# UCube_v2_Tower2.net
KiCad netlist of a schematic drawn in EAGLE
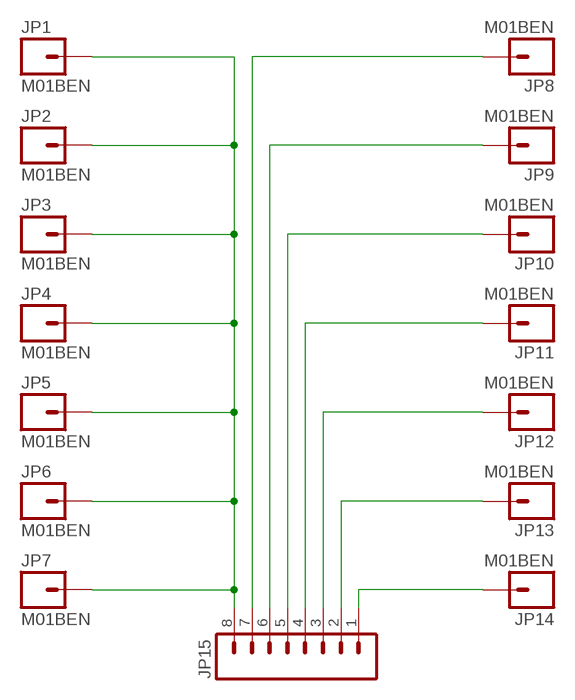
[diagram p0: schematic, sheet 1]

(export (version "E")
  (design (tool "Eeschema 10.0.6"))
  (components
    (comp (ref "JP1")
      (value "M01BEN")
      (footprint "eagle-import:1X01-BEN")
      (libsource (lib "eagle-import") (part "M01BEN"))
    )
    (comp (ref "JP2")
      (value "M01BEN")
      (footprint "eagle-import:1X01-BEN")
      (libsource (lib "eagle-import") (part "M01BEN"))
    )
    (comp (ref "JP3")
      (value "M01BEN")
      (footprint "eagle-import:1X01-BEN")
      (libsource (lib "eagle-import") (part "M01BEN"))
    )
    (comp (ref "JP4")
      (value "M01BEN")
      (footprint "eagle-import:1X01-BEN")
      (libsource (lib "eagle-import") (part "M01BEN"))
    )
    (comp (ref "JP5")
      (value "M01BEN")
      (footprint "eagle-import:1X01-BEN")
      (libsource (lib "eagle-import") (part "M01BEN"))
    )
    (comp (ref "JP6")
      (value "M01BEN")
      (footprint "eagle-import:1X01-BEN")
      (libsource (lib "eagle-import") (part "M01BEN"))
    )
    (comp (ref "JP7")
      (value "M01BEN")
      (footprint "eagle-import:1X01-BEN")
      (libsource (lib "eagle-import") (part "M01BEN"))
    )
    (comp (ref "JP8")
      (value "M01BEN")
      (footprint "eagle-import:1X01-BEN")
      (libsource (lib "eagle-import") (part "M01BEN"))
    )
    (comp (ref "JP9")
      (value "M01BEN")
      (footprint "eagle-import:1X01-BEN")
      (libsource (lib "eagle-import") (part "M01BEN"))
    )
    (comp (ref "JP10")
      (value "M01BEN")
      (footprint "eagle-import:1X01-BEN")
      (libsource (lib "eagle-import") (part "M01BEN"))
    )
    (comp (ref "JP11")
      (value "M01BEN")
      (footprint "eagle-import:1X01-BEN")
      (libsource (lib "eagle-import") (part "M01BEN"))
    )
    (comp (ref "JP12")
      (value "M01BEN")
      (footprint "eagle-import:1X01-BEN")
      (libsource (lib "eagle-import") (part "M01BEN"))
    )
    (comp (ref "JP13")
      (value "M01BEN")
      (footprint "eagle-import:1X01-BEN")
      (libsource (lib "eagle-import") (part "M01BEN"))
    )
    (comp (ref "JP14")
      (value "M01BEN")
      (footprint "eagle-import:1X01-BEN")
      (libsource (lib "eagle-import") (part "M01BEN"))
    )
    (comp (ref "JP15")
      (value "M081X08")
      (footprint "eagle-import:1X08")
      (libsource (lib "eagle-import") (part "M081X08"))
    )
  )
  (nets
    (net (code "1") (name "Net-(JP1-Pad1)") (class "Default")
      (node (ref "JP1") (pin "1") (pinfunction "1_1") (pintype "passive"))
      (node (ref "JP15") (pin "8") (pinfunction "8_8") (pintype "passive"))
      (node (ref "JP2") (pin "1") (pinfunction "1_1") (pintype "passive"))
      (node (ref "JP3") (pin "1") (pinfunction "1_1") (pintype "passive"))
      (node (ref "JP4") (pin "1") (pinfunction "1_1") (pintype "passive"))
      (node (ref "JP5") (pin "1") (pinfunction "1_1") (pintype "passive"))
      (node (ref "JP6") (pin "1") (pinfunction "1_1") (pintype "passive"))
      (node (ref "JP7") (pin "1") (pinfunction "1_1") (pintype "passive"))
    )
    (net (code "2") (name "Net-(JP10-Pad1)") (class "Default")
      (node (ref "JP10") (pin "1") (pinfunction "1_1") (pintype "passive"))
      (node (ref "JP15") (pin "5") (pinfunction "5_5") (pintype "passive"))
    )
    (net (code "3") (name "Net-(JP11-Pad1)") (class "Default")
      (node (ref "JP11") (pin "1") (pinfunction "1_1") (pintype "passive"))
      (node (ref "JP15") (pin "4") (pinfunction "4_4") (pintype "passive"))
    )
    (net (code "4") (name "Net-(JP12-Pad1)") (class "Default")
      (node (ref "JP12") (pin "1") (pinfunction "1_1") (pintype "passive"))
      (node (ref "JP15") (pin "3") (pinfunction "3_3") (pintype "passive"))
    )
    (net (code "5") (name "Net-(JP13-Pad1)") (class "Default")
      (node (ref "JP13") (pin "1") (pinfunction "1_1") (pintype "passive"))
      (node (ref "JP15") (pin "2") (pinfunction "2_2") (pintype "passive"))
    )
    (net (code "6") (name "Net-(JP14-Pad1)") (class "Default")
      (node (ref "JP14") (pin "1") (pinfunction "1_1") (pintype "passive"))
      (node (ref "JP15") (pin "1") (pinfunction "1_1") (pintype "passive"))
    )
    (net (code "7") (name "Net-(JP15-Pad6)") (class "Default")
      (node (ref "JP15") (pin "6") (pinfunction "6_6") (pintype "passive"))
      (node (ref "JP9") (pin "1") (pinfunction "1_1") (pintype "passive"))
    )
    (net (code "8") (name "Net-(JP15-Pad7)") (class "Default")
      (node (ref "JP15") (pin "7") (pinfunction "7_7") (pintype "passive"))
      (node (ref "JP8") (pin "1") (pinfunction "1_1") (pintype "passive"))
    )
  )
)
